# DAWA-MPU_6_3.net
KiCad netlist of a schematic drawn in EAGLE
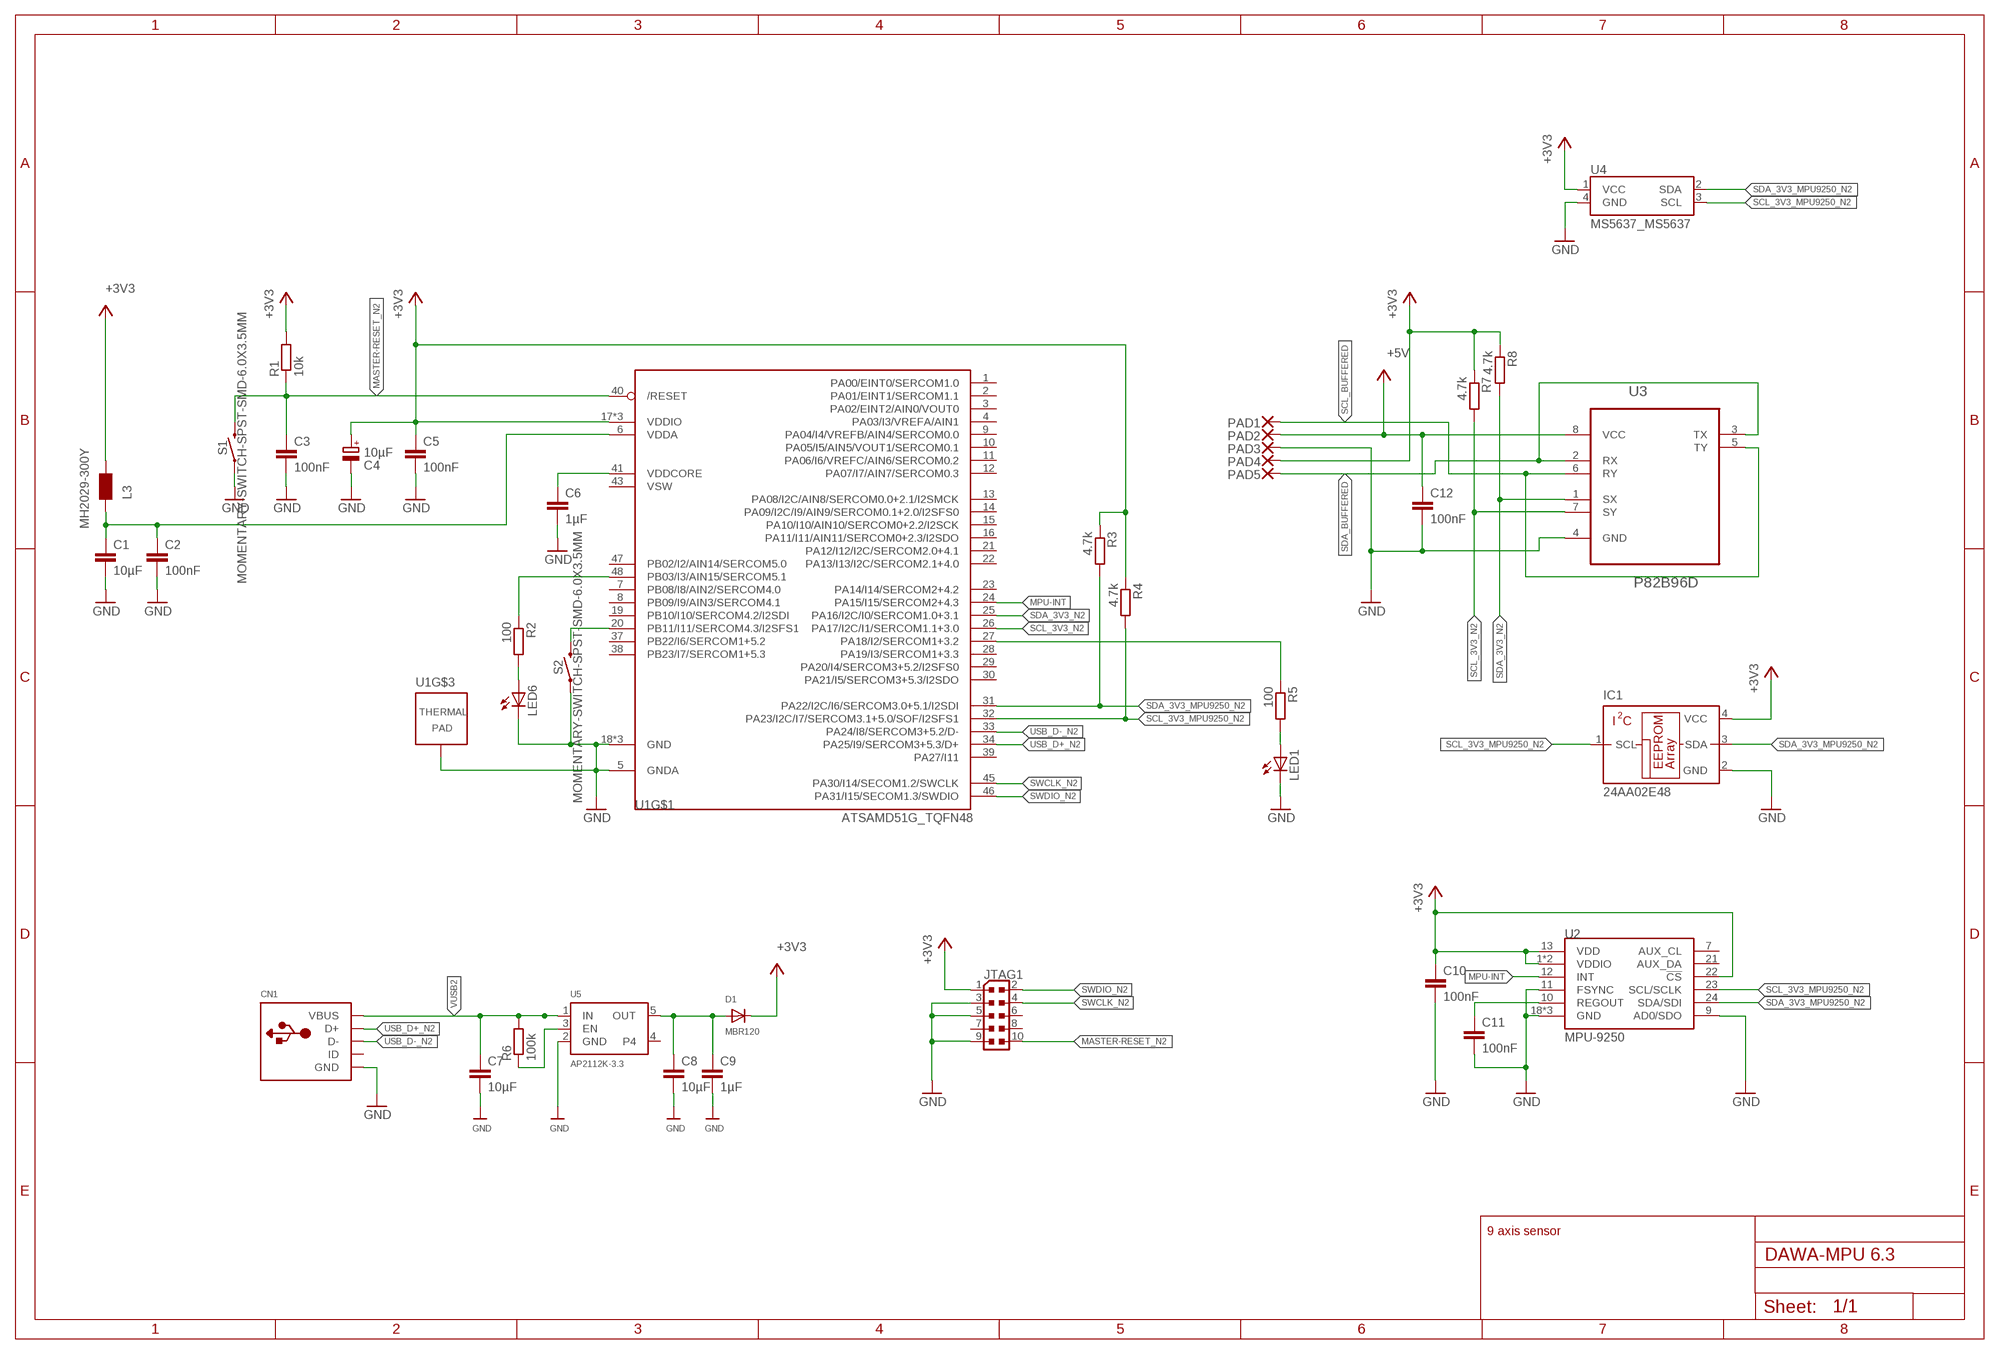
[diagram p0: schematic, sheet 1]

(export (version "E")
  (design (tool "Eeschema 10.0.6"))
  (components
    (comp (ref "C1")
      (value "10µF")
      (footprint "eagle-import:C0805")
      (libsource (lib "eagle-import") (part "rcl_334_C-EUC0805"))
    )
    (comp (ref "C2")
      (value "100nF")
      (footprint "eagle-import:C0603")
      (libsource (lib "eagle-import") (part "rcl_334_C-EUC0603"))
    )
    (comp (ref "C3")
      (value "100nF")
      (footprint "eagle-import:C0603")
      (libsource (lib "eagle-import") (part "rcl_334_C-EUC0603"))
    )
    (comp (ref "C4")
      (value "10µF")
      (footprint "eagle-import:SMC_B")
      (fields (field (name "SPICEPREFIX") "C"))
      (libsource (lib "eagle-import") (part "CPOL-EUSMCB"))
    )
    (comp (ref "C5")
      (value "100nF")
      (footprint "eagle-import:C0603")
      (libsource (lib "eagle-import") (part "rcl_334_C-EUC0603"))
    )
    (comp (ref "C6")
      (value "1µF")
      (footprint "eagle-import:C0603")
      (libsource (lib "eagle-import") (part "rcl_334_C-EUC0603"))
    )
    (comp (ref "C7")
      (value "10µF")
      (footprint "eagle-import:C0603")
      (libsource (lib "eagle-import") (part "rcl_334_C-EUC0603"))
    )
    (comp (ref "C8")
      (value "10µF")
      (footprint "eagle-import:C0603")
      (libsource (lib "eagle-import") (part "rcl_334_C-EUC0603"))
    )
    (comp (ref "C9")
      (value "1µF")
      (footprint "eagle-import:C0603")
      (libsource (lib "eagle-import") (part "rcl_334_C-EUC0603"))
    )
    (comp (ref "C10")
      (value "100nF")
      (footprint "eagle-import:C0603")
      (libsource (lib "eagle-import") (part "rcl_334_C-EUC0603"))
    )
    (comp (ref "C11")
      (value "100nF")
      (footprint "eagle-import:C0603")
      (libsource (lib "eagle-import") (part "rcl_334_C-EUC0603"))
    )
    (comp (ref "C12")
      (value "100nF")
      (footprint "eagle-import:C0603")
      (libsource (lib "eagle-import") (part "C-EUC0603"))
    )
    (comp (ref "CN1")
      (value "USB")
      (footprint "eagle-import:USB-MINIB-DAWA")
      (libsource (lib "eagle-import") (part "USB"))
    )
    (comp (ref "D1")
      (value "MBR120")
      (footprint "eagle-import:SOD-123FL")
      (libsource (lib "eagle-import") (part "DIODE_SOD-123FL"))
    )
    (comp (ref "IC1")
      (value "24AA02E48")
      (footprint "eagle-import:SOT23-5L")
      (fields (field (name "MF") "MICROCHIP") (field (name "MPN") "24AA00T-I/OTG"))
      (libsource (lib "eagle-import") (part "2400OTAA"))
    )
    (comp (ref "JTAG1")
      (value "PINHEAD_PINHD-2X5PASSO127")
      (footprint "eagle-import:PINHEAD_2X05_127")
      (libsource (lib "eagle-import") (part "PINHEAD_PINHD-2X5PASSO127"))
    )
    (comp (ref "L3")
      (value "MH2029-300Y")
      (footprint "eagle-import:0805")
      (libsource (lib "eagle-import") (part "WE-CBF_0805"))
    )
    (comp (ref "LED1")
      (value "LEDCHIPLED_1206")
      (footprint "eagle-import:CHIPLED_1206")
      (libsource (lib "eagle-import") (part "LEDCHIPLED_1206"))
    )
    (comp (ref "LED6")
      (value "LEDCHIPLED_1206")
      (footprint "eagle-import:CHIPLED_1206")
      (libsource (lib "eagle-import") (part "LEDCHIPLED_1206"))
    )
    (comp (ref "PAD1")
      (value "WIREPAD1,6/0,9")
      (footprint "eagle-import:1,6_0,9")
      (libsource (lib "eagle-import") (part "WIREPAD1,6/0,9"))
    )
    (comp (ref "PAD2")
      (value "WIREPAD1,6/0,9")
      (footprint "eagle-import:1,6_0,9")
      (libsource (lib "eagle-import") (part "WIREPAD1,6/0,9"))
    )
    (comp (ref "PAD3")
      (value "WIREPAD1,6/0,9")
      (footprint "eagle-import:1,6_0,9")
      (libsource (lib "eagle-import") (part "WIREPAD1,6/0,9"))
    )
    (comp (ref "PAD4")
      (value "WIREPAD1,6/0,9")
      (footprint "eagle-import:1,6_0,9")
      (libsource (lib "eagle-import") (part "WIREPAD1,6/0,9"))
    )
    (comp (ref "PAD5")
      (value "WIREPAD1,6/0,9")
      (footprint "eagle-import:1,6_0,9")
      (libsource (lib "eagle-import") (part "WIREPAD1,6/0,9"))
    )
    (comp (ref "R1")
      (value "10k")
      (footprint "eagle-import:R0603")
      (libsource (lib "eagle-import") (part "R-EU_R0603"))
    )
    (comp (ref "R2")
      (value "100")
      (footprint "eagle-import:R0603")
      (libsource (lib "eagle-import") (part "resistor_R-EU_R0603"))
    )
    (comp (ref "R3")
      (value "4.7k")
      (footprint "eagle-import:R0603")
      (libsource (lib "eagle-import") (part "resistor_R-EU_R0603"))
    )
    (comp (ref "R4")
      (value "4.7k")
      (footprint "eagle-import:R0603")
      (libsource (lib "eagle-import") (part "resistor_R-EU_R0603"))
    )
    (comp (ref "R5")
      (value "100")
      (footprint "eagle-import:R0603")
      (libsource (lib "eagle-import") (part "resistor_R-EU_R0603"))
    )
    (comp (ref "R6")
      (value "100k")
      (footprint "eagle-import:R0603")
      (libsource (lib "eagle-import") (part "R-EU_R0603"))
    )
    (comp (ref "R7")
      (value "4.7k")
      (footprint "eagle-import:R0603")
      (libsource (lib "eagle-import") (part "resistor_R-EU_R0603"))
    )
    (comp (ref "R8")
      (value "4.7k")
      (footprint "eagle-import:R0603")
      (libsource (lib "eagle-import") (part "resistor_R-EU_R0603"))
    )
    (comp (ref "S1")
      (value "MOMENTARY-SWITCH-SPST-SMD-6.0X3.5MM")
      (footprint "eagle-import:TACTILE_SWITCH_SMD_6.0X3.5MM")
      (libsource (lib "eagle-import") (part "MOMENTARY-SWITCH-SPST-SMD-6.0X3.5MM"))
    )
    (comp (ref "S2")
      (value "MOMENTARY-SWITCH-SPST-SMD-6.0X3.5MM")
      (footprint "eagle-import:TACTILE_SWITCH_SMD_6.0X3.5MM")
      (libsource (lib "eagle-import") (part "MOMENTARY-SWITCH-SPST-SMD-6.0X3.5MM"))
    )
    (comp (ref "U1")
      (value "ATSAMD51G_TQFN48")
      (footprint "eagle-import:TQFN48_7MM")
      (libsource (lib "eagle-import") (part "ATSAMD51G_TQFN48"))
    )
    (comp (ref "U2")
      (value "MPU-9250")
      (footprint "eagle-import:QFN24_PAD")
      (libsource (lib "eagle-import") (part "MPU-9250"))
    )
    (comp (ref "U3")
      (value "P82B96D")
      (footprint "eagle-import:SOIC127P600X175-8N")
      (libsource (lib "eagle-import") (part "P82B96D"))
    )
    (comp (ref "U4")
      (value "MS5637_MS5637")
      (footprint "eagle-import:MS5637_MS5637")
      (libsource (lib "eagle-import") (part "MS5637_MS5637"))
    )
    (comp (ref "U5")
      (value "AP2112K-3.3")
      (footprint "eagle-import:SOT23-5")
      (libsource (lib "eagle-import") (part "VREG_SOT23-5"))
    )
  )
  (nets
    (net (code "1") (name "+3V3") (class "Default")
      (node (ref "C10") (pin "1") (pinfunction "1_1") (pintype "passive"))
      (node (ref "C4") (pin "+") (pinfunction "+_+") (pintype "passive"))
      (node (ref "C5") (pin "1") (pinfunction "1_1") (pintype "passive"))
      (node (ref "D1") (pin "C") (pinfunction "C_C") (pintype "passive"))
      (node (ref "IC1") (pin "4") (pinfunction "VCC_4") (pintype "power_in"))
      (node (ref "JTAG1") (pin "1") (pinfunction "1_1") (pintype "passive"))
      (node (ref "L3") (pin "1") (pinfunction "1_1") (pintype "passive"))
      (node (ref "PAD4") (pin "1") (pinfunction "P_1") (pintype "passive"))
      (node (ref "R1") (pin "2") (pinfunction "2_2") (pintype "passive"))
      (node (ref "R3") (pin "1") (pinfunction "1_1") (pintype "passive"))
      (node (ref "R4") (pin "1") (pinfunction "1_1") (pintype "passive"))
      (node (ref "R7") (pin "1") (pinfunction "1_1") (pintype "passive"))
      (node (ref "R8") (pin "1") (pinfunction "1_1") (pintype "passive"))
      (node (ref "U1") (pin "17") (pinfunction "VDDIO_17") (pintype "power_in"))
      (node (ref "U1") (pin "36") (pinfunction "VDDIO_36") (pintype "power_in"))
      (node (ref "U1") (pin "44") (pinfunction "VDDIO_44") (pintype "power_in"))
      (node (ref "U2") (pin "1") (pinfunction "VDDIO_1") (pintype "bidirectional"))
      (node (ref "U2") (pin "13") (pinfunction "VDD_13") (pintype "bidirectional"))
      (node (ref "U2") (pin "22") (pinfunction "~{CS}_22") (pintype "bidirectional"))
      (node (ref "U2") (pin "8") (pinfunction "VDDIO_8") (pintype "bidirectional"))
      (node (ref "U4") (pin "1") (pinfunction "VCC_1") (pintype "bidirectional"))
    )
    (net (code "2") (name "+5V") (class "Default")
      (node (ref "C12") (pin "1") (pinfunction "1_1") (pintype "passive"))
      (node (ref "PAD2") (pin "1") (pinfunction "P_1") (pintype "passive"))
      (node (ref "U3") (pin "8") (pinfunction "VCC_8") (pintype "power_in"))
    )
    (net (code "3") (name "/VSW") (class "Default")
      (node (ref "U1") (pin "43") (pinfunction "VSW_43") (pintype "power_in"))
    )
    (net (code "4") (name "GND") (class "Default")
      (node (ref "C1") (pin "2") (pinfunction "2_2") (pintype "passive"))
      (node (ref "C10") (pin "2") (pinfunction "2_2") (pintype "passive"))
      (node (ref "C11") (pin "2") (pinfunction "2_2") (pintype "passive"))
      (node (ref "C12") (pin "2") (pinfunction "2_2") (pintype "passive"))
      (node (ref "C2") (pin "2") (pinfunction "2_2") (pintype "passive"))
      (node (ref "C3") (pin "2") (pinfunction "2_2") (pintype "passive"))
      (node (ref "C4") (pin "-") (pinfunction "-_-") (pintype "passive"))
      (node (ref "C5") (pin "2") (pinfunction "2_2") (pintype "passive"))
      (node (ref "C6") (pin "2") (pinfunction "2_2") (pintype "passive"))
      (node (ref "C7") (pin "2") (pinfunction "2_2") (pintype "passive"))
      (node (ref "C8") (pin "2") (pinfunction "2_2") (pintype "passive"))
      (node (ref "C9") (pin "2") (pinfunction "2_2") (pintype "passive"))
      (node (ref "CN1") (pin "GND") (pinfunction "GND_GND") (pintype "power_in"))
      (node (ref "CN1") (pin "GND1") (pinfunction "GND_GND1") (pintype "power_in"))
      (node (ref "CN1") (pin "GND2") (pinfunction "GND_GND2") (pintype "power_in"))
      (node (ref "IC1") (pin "2") (pinfunction "GND_2") (pintype "power_in"))
      (node (ref "JTAG1") (pin "3") (pinfunction "3_3") (pintype "passive"))
      (node (ref "JTAG1") (pin "5") (pinfunction "5_5") (pintype "passive"))
      (node (ref "JTAG1") (pin "9") (pinfunction "9_9") (pintype "passive"))
      (node (ref "LED1") (pin "C") (pinfunction "C_C") (pintype "passive"))
      (node (ref "LED6") (pin "C") (pinfunction "C_C") (pintype "passive"))
      (node (ref "PAD3") (pin "1") (pinfunction "P_1") (pintype "passive"))
      (node (ref "S1") (pin "1") (pinfunction "1_1") (pintype "passive"))
      (node (ref "S2") (pin "1") (pinfunction "1_1") (pintype "passive"))
      (node (ref "U1") (pin "18") (pinfunction "GND_18") (pintype "power_in"))
      (node (ref "U1") (pin "35") (pinfunction "GND_35") (pintype "power_in"))
      (node (ref "U1") (pin "42") (pinfunction "GND_42") (pintype "power_in"))
      (node (ref "U1") (pin "5") (pinfunction "GNDA_5") (pintype "power_in"))
      (node (ref "U1") (pin "THERMAL") (pinfunction "TP_THERMAL") (pintype "power_in"))
      (node (ref "U2") (pin "11") (pinfunction "FSYNC_11") (pintype "bidirectional"))
      (node (ref "U2") (pin "18") (pinfunction "GND_18") (pintype "bidirectional"))
      (node (ref "U2") (pin "20") (pinfunction "GND_20") (pintype "bidirectional"))
      (node (ref "U2") (pin "9") (pinfunction "AD0/SDO_9") (pintype "bidirectional"))
      (node (ref "U2") (pin "CENTER") (pinfunction "GND_CENTER") (pintype "bidirectional"))
      (node (ref "U3") (pin "4") (pinfunction "GND_4") (pintype "passive"))
      (node (ref "U4") (pin "4") (pinfunction "GND_4") (pintype "bidirectional"))
      (node (ref "U5") (pin "2") (pinfunction "GND_2") (pintype "power_in"))
    )
    (net (code "5") (name "MASTER-RESET_N2") (class "Default")
      (node (ref "C3") (pin "1") (pinfunction "1_1") (pintype "passive"))
      (node (ref "JTAG1") (pin "10") (pinfunction "10_10") (pintype "passive"))
      (node (ref "R1") (pin "1") (pinfunction "1_1") (pintype "passive"))
      (node (ref "S1") (pin "2") (pinfunction "2_2") (pintype "passive"))
      (node (ref "U1") (pin "40") (pinfunction "/RESET_40") (pintype "bidirectional"))
    )
    (net (code "6") (name "MPU-INT") (class "Default")
      (node (ref "U1") (pin "24") (pinfunction "PA15/I15/SERCOM2+4.3_24") (pintype "bidirectional"))
      (node (ref "U2") (pin "12") (pinfunction "INT_12") (pintype "bidirectional"))
    )
    (net (code "7") (name "Net-(LED1-PadA)") (class "Default")
      (node (ref "LED1") (pin "A") (pinfunction "A_A") (pintype "passive"))
      (node (ref "R5") (pin "2") (pinfunction "2_2") (pintype "passive"))
    )
    (net (code "8") (name "Net-(LED6-PadA)") (class "Default")
      (node (ref "LED6") (pin "A") (pinfunction "A_A") (pintype "passive"))
      (node (ref "R2") (pin "2") (pinfunction "2_2") (pintype "passive"))
    )
    (net (code "9") (name "Net-(U1A-PA18{slash}I2{slash}SERCOM1+3.2)") (class "Default")
      (node (ref "R5") (pin "1") (pinfunction "1_1") (pintype "passive"))
      (node (ref "U1") (pin "27") (pinfunction "PA18/I2/SERCOM1+3.2_27") (pintype "bidirectional"))
    )
    (net (code "10") (name "Net-(U1A-PB03{slash}I3{slash}AIN15{slash}SERCOM5.1)") (class "Default")
      (node (ref "R2") (pin "1") (pinfunction "1_1") (pintype "passive"))
      (node (ref "U1") (pin "48") (pinfunction "PB03/I3/AIN15/SERCOM5.1_48") (pintype "bidirectional"))
    )
    (net (code "11") (name "Net-(U1A-PB11{slash}I11{slash}SERCOM4.3{slash}I2SFS1)") (class "Default")
      (node (ref "S2") (pin "2") (pinfunction "2_2") (pintype "passive"))
      (node (ref "U1") (pin "20") (pinfunction "PB11/I11/SERCOM4.3/I2SFS1_20") (pintype "bidirectional"))
    )
    (net (code "12") (name "Net-(U1A-VDDA)") (class "Default")
      (node (ref "C1") (pin "1") (pinfunction "1_1") (pintype "passive"))
      (node (ref "C2") (pin "1") (pinfunction "1_1") (pintype "passive"))
      (node (ref "L3") (pin "2") (pinfunction "2_2") (pintype "passive"))
      (node (ref "U1") (pin "6") (pinfunction "VDDA_6") (pintype "power_in"))
    )
    (net (code "13") (name "Net-(U1A-VDDCORE)") (class "Default")
      (node (ref "C6") (pin "1") (pinfunction "1_1") (pintype "passive"))
      (node (ref "U1") (pin "41") (pinfunction "VDDCORE_41") (pintype "power_in"))
    )
    (net (code "14") (name "Net-(U2-REGOUT)") (class "Default")
      (node (ref "C11") (pin "1") (pinfunction "1_1") (pintype "passive"))
      (node (ref "U2") (pin "10") (pinfunction "REGOUT_10") (pintype "bidirectional"))
    )
    (net (code "15") (name "Net-(U5-EN)") (class "Default")
      (node (ref "R6") (pin "1") (pinfunction "1_1") (pintype "passive"))
      (node (ref "U5") (pin "3") (pinfunction "EN_3") (pintype "input"))
    )
    (net (code "16") (name "Net-(U5-OUT)") (class "Default")
      (node (ref "C8") (pin "1") (pinfunction "1_1") (pintype "passive"))
      (node (ref "C9") (pin "1") (pinfunction "1_1") (pintype "passive"))
      (node (ref "D1") (pin "A") (pinfunction "A_A") (pintype "passive"))
      (node (ref "U5") (pin "5") (pinfunction "OUT_5") (pintype "power_in"))
    )
    (net (code "17") (name "SCL_3V3_MPU9250_N2") (class "Default")
      (node (ref "IC1") (pin "1") (pinfunction "SCL_1") (pintype "input"))
      (node (ref "R4") (pin "2") (pinfunction "2_2") (pintype "passive"))
      (node (ref "U1") (pin "32") (pinfunction "PA23/I2C/I7/SERCOM3.1+5.0/SOF/I2SFS1_32") (pintype "bidirectional"))
      (node (ref "U2") (pin "23") (pinfunction "SCL/SCLK_23") (pintype "bidirectional"))
      (node (ref "U4") (pin "3") (pinfunction "SCL_3") (pintype "bidirectional"))
    )
    (net (code "18") (name "SCL_3V3_N2") (class "Default")
      (node (ref "R7") (pin "2") (pinfunction "2_2") (pintype "passive"))
      (node (ref "U1") (pin "26") (pinfunction "PA17/I2C/I1/SERCOM1.1+3.0_26") (pintype "bidirectional"))
      (node (ref "U3") (pin "7") (pinfunction "SY_7") (pintype "input"))
    )
    (net (code "19") (name "SCL_BUFFERED") (class "Default")
      (node (ref "PAD1") (pin "1") (pinfunction "P_1") (pintype "passive"))
      (node (ref "U3") (pin "5") (pinfunction "TY_5") (pintype "output"))
      (node (ref "U3") (pin "6") (pinfunction "RY_6") (pintype "input"))
    )
    (net (code "20") (name "SDA_3V3_MPU9250_N2") (class "Default")
      (node (ref "IC1") (pin "3") (pinfunction "SDA_3") (pintype "bidirectional"))
      (node (ref "R3") (pin "2") (pinfunction "2_2") (pintype "passive"))
      (node (ref "U1") (pin "31") (pinfunction "PA22/I2C/I6/SERCOM3.0+5.1/I2SDI_31") (pintype "bidirectional"))
      (node (ref "U2") (pin "24") (pinfunction "SDA/SDI_24") (pintype "bidirectional"))
      (node (ref "U4") (pin "2") (pinfunction "SDA_2") (pintype "bidirectional"))
    )
    (net (code "21") (name "SDA_3V3_N2") (class "Default")
      (node (ref "R8") (pin "2") (pinfunction "2_2") (pintype "passive"))
      (node (ref "U1") (pin "25") (pinfunction "PA16/I2C/I0/SERCOM1.0+3.1_25") (pintype "bidirectional"))
      (node (ref "U3") (pin "1") (pinfunction "SX_1") (pintype "input"))
    )
    (net (code "22") (name "SDA_BUFFERED") (class "Default")
      (node (ref "PAD5") (pin "1") (pinfunction "P_1") (pintype "passive"))
      (node (ref "U3") (pin "2") (pinfunction "RX_2") (pintype "input"))
      (node (ref "U3") (pin "3") (pinfunction "TX_3") (pintype "output"))
    )
    (net (code "23") (name "SWCLK_N2") (class "Default")
      (node (ref "JTAG1") (pin "4") (pinfunction "4_4") (pintype "passive"))
      (node (ref "U1") (pin "45") (pinfunction "PA30/I14/SECOM1.2/SWCLK_45") (pintype "bidirectional"))
    )
    (net (code "24") (name "SWDIO_N2") (class "Default")
      (node (ref "JTAG1") (pin "2") (pinfunction "2_2") (pintype "passive"))
      (node (ref "U1") (pin "46") (pinfunction "PA31/I15/SECOM1.3/SWDIO_46") (pintype "bidirectional"))
    )
    (net (code "25") (name "USB_D+_N2") (class "Default")
      (node (ref "CN1") (pin "D+") (pinfunction "D+_D+") (pintype "bidirectional"))
      (node (ref "U1") (pin "34") (pinfunction "PA25/I9/SERCOM3+5.3/D+_34") (pintype "bidirectional"))
    )
    (net (code "26") (name "USB_D-_N2") (class "Default")
      (node (ref "CN1") (pin "D-") (pinfunction "D-_D-") (pintype "bidirectional"))
      (node (ref "U1") (pin "33") (pinfunction "PA24/I8/SERCOM3+5.2/D-_33") (pintype "bidirectional"))
    )
    (net (code "27") (name "VUSB2") (class "Default")
      (node (ref "C7") (pin "1") (pinfunction "1_1") (pintype "passive"))
      (node (ref "CN1") (pin "VBUS") (pinfunction "VBUS_VBUS") (pintype "power_in"))
      (node (ref "R6") (pin "2") (pinfunction "2_2") (pintype "passive"))
      (node (ref "U5") (pin "1") (pinfunction "IN_1") (pintype "power_in"))
    )
    (net (code "28") (name "unconnected-(CN1-PadID)") (class "Default")
      (node (ref "CN1") (pin "ID") (pinfunction "ID_ID") (pintype "bidirectional"))
    )
    (net (code "29") (name "unconnected-(JTAG1-Pad6)") (class "Default")
      (node (ref "JTAG1") (pin "6") (pinfunction "6_6") (pintype "passive"))
    )
    (net (code "30") (name "unconnected-(JTAG1-Pad7)") (class "Default")
      (node (ref "JTAG1") (pin "7") (pinfunction "7_7") (pintype "passive"))
    )
    (net (code "31") (name "unconnected-(JTAG1-Pad8)") (class "Default")
      (node (ref "JTAG1") (pin "8") (pinfunction "8_8") (pintype "passive"))
    )
    (net (code "32") (name "unconnected-(U1A-PA00{slash}EINT0{slash}SERCOM1.0-Pad1)") (class "Default")
      (node (ref "U1") (pin "1") (pinfunction "PA00/EINT0/SERCOM1.0_1") (pintype "bidirectional"))
    )
    (net (code "33") (name "unconnected-(U1A-PA01{slash}EINT1{slash}SERCOM1.1-Pad2)") (class "Default")
      (node (ref "U1") (pin "2") (pinfunction "PA01/EINT1/SERCOM1.1_2") (pintype "bidirectional"))
    )
    (net (code "34") (name "unconnected-(U1A-PA02{slash}EINT2{slash}AIN0{slash}VOUT0-Pad3)") (class "Default")
      (node (ref "U1") (pin "3") (pinfunction "PA02/EINT2/AIN0/VOUT0_3") (pintype "bidirectional"))
    )
    (net (code "35") (name "unconnected-(U1A-PA03{slash}I3{slash}VREFA{slash}AIN1-Pad4)") (class "Default")
      (node (ref "U1") (pin "4") (pinfunction "PA03/I3/VREFA/AIN1_4") (pintype "bidirectional"))
    )
    (net (code "36") (name "unconnected-(U1A-PA04{slash}I4{slash}VREFB{slash}AIN4{slash}SERCOM0.0-Pad9)") (class "Default")
      (node (ref "U1") (pin "9") (pinfunction "PA04/I4/VREFB/AIN4/SERCOM0.0_9") (pintype "bidirectional"))
    )
    (net (code "37") (name "unconnected-(U1A-PA05{slash}I5{slash}AIN5{slash}VOUT1{slash}SERCOM0.1-Pad10)") (class "Default")
      (node (ref "U1") (pin "10") (pinfunction "PA05/I5/AIN5/VOUT1/SERCOM0.1_10") (pintype "bidirectional"))
    )
    (net (code "38") (name "unconnected-(U1A-PA06{slash}I6{slash}VREFC{slash}AIN6{slash}SERCOM0.2-Pad11)") (class "Default")
      (node (ref "U1") (pin "11") (pinfunction "PA06/I6/VREFC/AIN6/SERCOM0.2_11") (pintype "bidirectional"))
    )
    (net (code "39") (name "unconnected-(U1A-PA07{slash}I7{slash}AIN7{slash}SERCOM0.3-Pad12)") (class "Default")
      (node (ref "U1") (pin "12") (pinfunction "PA07/I7/AIN7/SERCOM0.3_12") (pintype "bidirectional"))
    )
    (net (code "40") (name "unconnected-(U1A-PA08{slash}I2C{slash}AIN8{slash}SERCOM0.0+2.1{slash}I2SMCK-Pad13)") (class "Default")
      (node (ref "U1") (pin "13") (pinfunction "PA08/I2C/AIN8/SERCOM0.0+2.1/I2SMCK_13") (pintype "bidirectional"))
    )
    (net (code "41") (name "unconnected-(U1A-PA09{slash}I2C{slash}I9{slash}AIN9{slash}SERCOM0.1+2.0{slash}I2SFS0-Pad14)") (class "Default")
      (node (ref "U1") (pin "14") (pinfunction "PA09/I2C/I9/AIN9/SERCOM0.1+2.0/I2SFS0_14") (pintype "bidirectional"))
    )
    (net (code "42") (name "unconnected-(U1A-PA10{slash}I10{slash}AIN10{slash}SERCOM0+2.2{slash}I2SCK-Pad15)") (class "Default")
      (node (ref "U1") (pin "15") (pinfunction "PA10/I10/AIN10/SERCOM0+2.2/I2SCK_15") (pintype "bidirectional"))
    )
    (net (code "43") (name "unconnected-(U1A-PA11{slash}I11{slash}AIN11{slash}SERCOM0+2.3{slash}I2SDO-Pad16)") (class "Default")
      (node (ref "U1") (pin "16") (pinfunction "PA11/I11/AIN11/SERCOM0+2.3/I2SDO_16") (pintype "bidirectional"))
    )
    (net (code "44") (name "unconnected-(U1A-PA12{slash}I12{slash}I2C{slash}SERCOM2.0+4.1-Pad21)") (class "Default")
      (node (ref "U1") (pin "21") (pinfunction "PA12/I12/I2C/SERCOM2.0+4.1_21") (pintype "bidirectional"))
    )
    (net (code "45") (name "unconnected-(U1A-PA13{slash}I13{slash}I2C{slash}SERCOM2.1+4.0-Pad22)") (class "Default")
      (node (ref "U1") (pin "22") (pinfunction "PA13/I13/I2C/SERCOM2.1+4.0_22") (pintype "bidirectional"))
    )
    (net (code "46") (name "unconnected-(U1A-PA14{slash}I14{slash}SERCOM2+4.2-Pad23)") (class "Default")
      (node (ref "U1") (pin "23") (pinfunction "PA14/I14/SERCOM2+4.2_23") (pintype "bidirectional"))
    )
    (net (code "47") (name "unconnected-(U1A-PA19{slash}I3{slash}SERCOM1+3.3-Pad28)") (class "Default")
      (node (ref "U1") (pin "28") (pinfunction "PA19/I3/SERCOM1+3.3_28") (pintype "bidirectional"))
    )
    (net (code "48") (name "unconnected-(U1A-PA20{slash}I4{slash}SERCOM3+5.2{slash}I2SFS0-Pad29)") (class "Default")
      (node (ref "U1") (pin "29") (pinfunction "PA20/I4/SERCOM3+5.2/I2SFS0_29") (pintype "bidirectional"))
    )
    (net (code "49") (name "unconnected-(U1A-PA21{slash}I5{slash}SERCOM3+5.3{slash}I2SDO-Pad30)") (class "Default")
      (node (ref "U1") (pin "30") (pinfunction "PA21/I5/SERCOM3+5.3/I2SDO_30") (pintype "bidirectional"))
    )
    (net (code "50") (name "unconnected-(U1A-PA27{slash}I11-Pad39)") (class "Default")
      (node (ref "U1") (pin "39") (pinfunction "PA27/I11_39") (pintype "bidirectional"))
    )
    (net (code "51") (name "unconnected-(U1A-PB02{slash}I2{slash}AIN14{slash}SERCOM5.0-Pad47)") (class "Default")
      (node (ref "U1") (pin "47") (pinfunction "PB02/I2/AIN14/SERCOM5.0_47") (pintype "bidirectional"))
    )
    (net (code "52") (name "unconnected-(U1A-PB08{slash}I8{slash}AIN2{slash}SERCOM4.0-Pad7)") (class "Default")
      (node (ref "U1") (pin "7") (pinfunction "PB08/I8/AIN2/SERCOM4.0_7") (pintype "bidirectional"))
    )
    (net (code "53") (name "unconnected-(U1A-PB09{slash}I9{slash}AIN3{slash}SERCOM4.1-Pad8)") (class "Default")
      (node (ref "U1") (pin "8") (pinfunction "PB09/I9/AIN3/SERCOM4.1_8") (pintype "bidirectional"))
    )
    (net (code "54") (name "unconnected-(U1A-PB10{slash}I10{slash}SERCOM4.2{slash}I2SDI-Pad19)") (class "Default")
      (node (ref "U1") (pin "19") (pinfunction "PB10/I10/SERCOM4.2/I2SDI_19") (pintype "bidirectional"))
    )
    (net (code "55") (name "unconnected-(U1A-PB22{slash}I6{slash}SERCOM1+5.2-Pad37)") (class "Default")
      (node (ref "U1") (pin "37") (pinfunction "PB22/I6/SERCOM1+5.2_37") (pintype "bidirectional"))
    )
    (net (code "56") (name "unconnected-(U1A-PB23{slash}I7{slash}SERCOM1+5.3-Pad38)") (class "Default")
      (node (ref "U1") (pin "38") (pinfunction "PB23/I7/SERCOM1+5.3_38") (pintype "bidirectional"))
    )
    (net (code "57") (name "unconnected-(U2-AUX_CL-Pad7)") (class "Default")
      (node (ref "U2") (pin "7") (pinfunction "AUX_CL_7") (pintype "bidirectional"))
    )
    (net (code "58") (name "unconnected-(U2-AUX_DA-Pad21)") (class "Default")
      (node (ref "U2") (pin "21") (pinfunction "AUX_DA_21") (pintype "bidirectional"))
    )
    (net (code "59") (name "unconnected-(U5-P4-Pad4)") (class "Default")
      (node (ref "U5") (pin "4") (pinfunction "P4_4") (pintype "bidirectional"))
    )
  )
)
